# RobotController.net
KiCad netlist of a schematic drawn in EAGLE
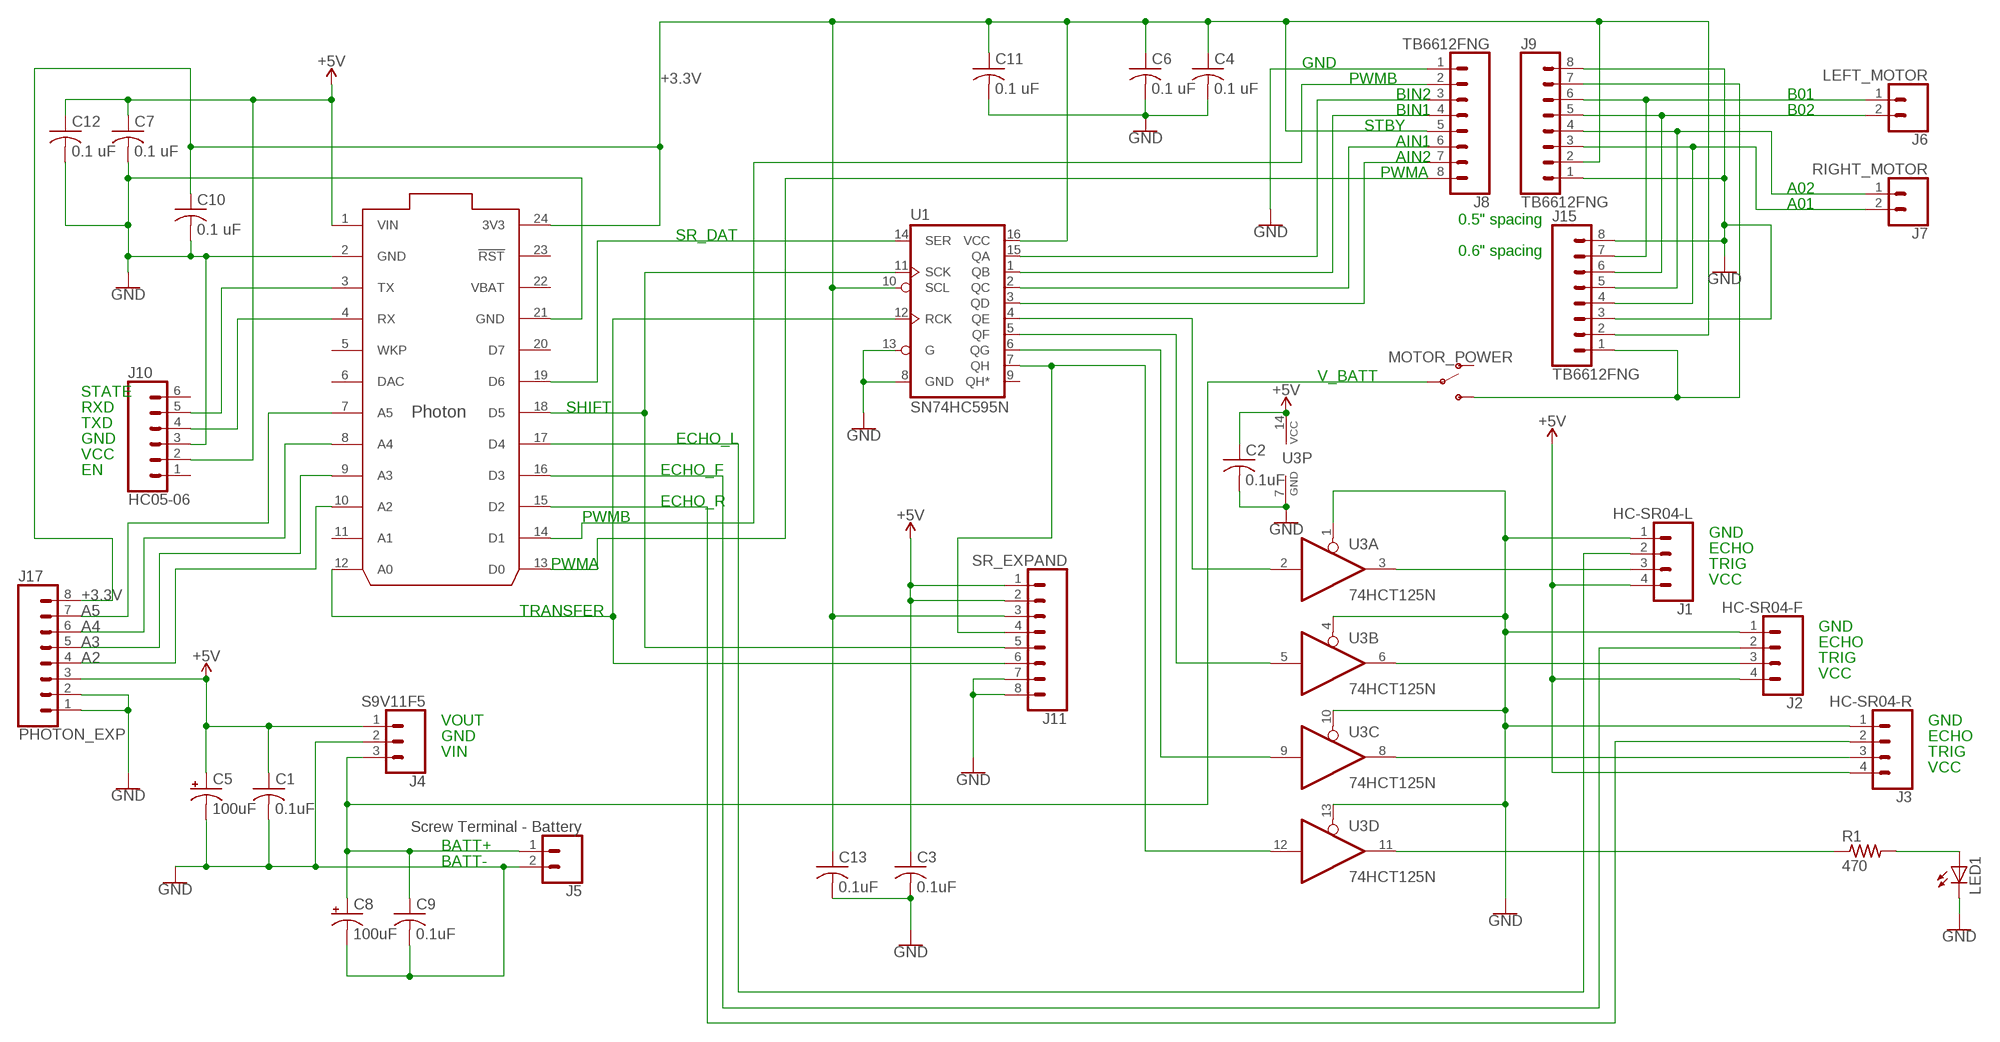
[diagram p0: schematic, sheet 1]

(export (version "E")
  (design (tool "Eeschema 10.0.6"))
  (components
    (comp (ref "C1")
      (value "0.1uF")
      (footprint "eagle-import:C025-024X044")
      (libsource (lib "eagle-import") (part "C-US025-024X044"))
    )
    (comp (ref "C2")
      (value "0.1uF")
      (footprint "eagle-import:C025-024X044")
      (libsource (lib "eagle-import") (part "C-US025-024X044"))
    )
    (comp (ref "C3")
      (value "0.1uF")
      (footprint "eagle-import:C025-024X044")
      (libsource (lib "eagle-import") (part "C-US025-024X044"))
    )
    (comp (ref "C4")
      (value "0.1 uF")
      (footprint "eagle-import:C025-024X044")
      (libsource (lib "eagle-import") (part "C-US025-024X044"))
    )
    (comp (ref "C5")
      (value "100uF")
      (footprint "eagle-import:E2,5-6E")
      (libsource (lib "eagle-import") (part "CPOL-USE2,5-6E"))
    )
    (comp (ref "C6")
      (value "0.1 uF")
      (footprint "eagle-import:C025-024X044")
      (libsource (lib "eagle-import") (part "C-US025-024X044"))
    )
    (comp (ref "C7")
      (value "0.1 uF")
      (footprint "eagle-import:C025-024X044")
      (libsource (lib "eagle-import") (part "C-US025-024X044"))
    )
    (comp (ref "C8")
      (value "100uF")
      (footprint "eagle-import:E2,5-6E")
      (libsource (lib "eagle-import") (part "CPOL-USE2,5-6E"))
    )
    (comp (ref "C9")
      (value "0.1uF")
      (footprint "eagle-import:C025-024X044")
      (libsource (lib "eagle-import") (part "C-US025-024X044"))
    )
    (comp (ref "C10")
      (value "0.1 uF")
      (footprint "eagle-import:C025-024X044")
      (libsource (lib "eagle-import") (part "C-US025-024X044"))
    )
    (comp (ref "C11")
      (value "0.1 uF")
      (footprint "eagle-import:C025-024X044")
      (libsource (lib "eagle-import") (part "C-US025-024X044"))
    )
    (comp (ref "C12")
      (value "0.1 uF")
      (footprint "eagle-import:C025-024X044")
      (libsource (lib "eagle-import") (part "C-US025-024X044"))
    )
    (comp (ref "C13")
      (value "0.1uF")
      (footprint "eagle-import:C025-024X044")
      (libsource (lib "eagle-import") (part "C-US025-024X044"))
    )
    (comp (ref "J1")
      (value "HC-SR04-L")
      (footprint "eagle-import:1X04")
      (libsource (lib "eagle-import") (part "CONN_04"))
    )
    (comp (ref "J2")
      (value "HC-SR04-F")
      (footprint "eagle-import:1X04")
      (libsource (lib "eagle-import") (part "CONN_04"))
    )
    (comp (ref "J3")
      (value "HC-SR04-R")
      (footprint "eagle-import:1X04")
      (libsource (lib "eagle-import") (part "CONN_04"))
    )
    (comp (ref "J4")
      (value "S9V11F5")
      (footprint "eagle-import:1X03")
      (libsource (lib "eagle-import") (part "CONN_03"))
    )
    (comp (ref "J5")
      (value "Screw Terminal - Battery")
      (footprint "eagle-import:SCREWTERMINAL-3.5MM-2")
      (libsource (lib "eagle-import") (part "CONN_023.5MM"))
    )
    (comp (ref "J6")
      (value "LEFT_MOTOR")
      (footprint "eagle-import:SCREWTERMINAL-3.5MM-2")
      (libsource (lib "eagle-import") (part "CONN_023.5MM"))
    )
    (comp (ref "J7")
      (value "RIGHT_MOTOR")
      (footprint "eagle-import:SCREWTERMINAL-3.5MM-2")
      (libsource (lib "eagle-import") (part "CONN_023.5MM"))
    )
    (comp (ref "J8")
      (value "TB6612FNG")
      (footprint "eagle-import:1X08")
      (libsource (lib "eagle-import") (part "CONN_08{dblquote}"))
    )
    (comp (ref "J9")
      (value "TB6612FNG")
      (footprint "eagle-import:1X08")
      (libsource (lib "eagle-import") (part "CONN_08{dblquote}"))
    )
    (comp (ref "J10")
      (value "HC05-06")
      (footprint "eagle-import:1X06")
      (libsource (lib "eagle-import") (part "CONN_06SILK_FEMALE_PTH"))
    )
    (comp (ref "J11")
      (value "SR_EXPAND")
      (footprint "eagle-import:1X08")
      (libsource (lib "eagle-import") (part "CONN_08{dblquote}"))
    )
    (comp (ref "J15")
      (value "TB6612FNG")
      (footprint "eagle-import:1X08")
      (libsource (lib "eagle-import") (part "CONN_08{dblquote}"))
    )
    (comp (ref "J17")
      (value "PHOTON_EXP")
      (footprint "eagle-import:1X08")
      (libsource (lib "eagle-import") (part "CONN_08{dblquote}"))
    )
    (comp (ref "LED1")
      (value "LED5MM")
      (footprint "eagle-import:LED5MM")
      (libsource (lib "eagle-import") (part "LED5MM"))
    )
    (comp (ref "MOTOR_POWER")
      (value "SWITCH-SPDT-PTH-11.6X4.0MM")
      (footprint "eagle-import:SWITCH_SPDT_PTH_11.6X4.0MM")
      (libsource (lib "eagle-import") (part "SWITCH-SPDT-PTH-11.6X4.0MM"))
    )
    (comp (ref "R1")
      (value "470")
      (footprint "eagle-import:0207_10")
      (libsource (lib "eagle-import") (part "R-US_0207/10"))
    )
    (comp (ref "U$1")
      (value "PHOTON_WITH_HEADERS")
      (footprint "eagle-import:PHOTON")
      (libsource (lib "eagle-import") (part "PHOTON_WITH_HEADERS"))
    )
    (comp (ref "U1")
      (value "SN74HC595N")
      (footprint "eagle-import:DIP16")
      (libsource (lib "eagle-import") (part "74595NHC"))
    )
    (comp (ref "U3")
      (value "74HCT125N")
      (footprint "eagle-import:DIL14")
      (libsource (lib "eagle-import") (part "74125NHCT"))
    )
  )
  (nets
    (net (code "1") (name "+5V") (class "Default")
      (node (ref "C1") (pin "1") (pinfunction "1_1") (pintype "passive"))
      (node (ref "C12") (pin "1") (pinfunction "1_1") (pintype "passive"))
      (node (ref "C2") (pin "1") (pinfunction "1_1") (pintype "passive"))
      (node (ref "C3") (pin "1") (pinfunction "1_1") (pintype "passive"))
      (node (ref "C5") (pin "+") (pinfunction "+_+") (pintype "passive"))
      (node (ref "C7") (pin "1") (pinfunction "1_1") (pintype "passive"))
      (node (ref "J1") (pin "4") (pinfunction "4_4") (pintype "passive"))
      (node (ref "J10") (pin "2") (pinfunction "2_2") (pintype "passive"))
      (node (ref "J11") (pin "1") (pinfunction "1_1") (pintype "passive"))
      (node (ref "J11") (pin "2") (pinfunction "2_2") (pintype "passive"))
      (node (ref "J17") (pin "3") (pinfunction "3_3") (pintype "passive"))
      (node (ref "J2") (pin "4") (pinfunction "4_4") (pintype "passive"))
      (node (ref "J3") (pin "4") (pinfunction "4_4") (pintype "passive"))
      (node (ref "J4") (pin "1") (pinfunction "1_1") (pintype "passive"))
      (node (ref "U$1") (pin "1") (pinfunction "VIN_1") (pintype "power_in"))
      (node (ref "U3") (pin "14") (pinfunction "VCC_14") (pintype "power_in"))
    )
    (net (code "2") (name "/+3.3V") (class "Default")
      (node (ref "C10") (pin "1") (pinfunction "1_1") (pintype "passive"))
      (node (ref "C11") (pin "1") (pinfunction "1_1") (pintype "passive"))
      (node (ref "C13") (pin "1") (pinfunction "1_1") (pintype "passive"))
      (node (ref "C4") (pin "1") (pinfunction "1_1") (pintype "passive"))
      (node (ref "C6") (pin "1") (pinfunction "1_1") (pintype "passive"))
      (node (ref "J11") (pin "3") (pinfunction "3_3") (pintype "passive"))
      (node (ref "J15") (pin "2") (pinfunction "2_2") (pintype "passive"))
      (node (ref "J17") (pin "8") (pinfunction "8_8") (pintype "passive"))
      (node (ref "J8") (pin "5") (pinfunction "5_5") (pintype "passive"))
      (node (ref "J9") (pin "2") (pinfunction "2_2") (pintype "passive"))
      (node (ref "U$1") (pin "24") (pinfunction "3V3_24") (pintype "power_in"))
      (node (ref "U1") (pin "10") (pinfunction "SCL_10") (pintype "input"))
      (node (ref "U1") (pin "16") (pinfunction "VCC_16") (pintype "power_in"))
    )
    (net (code "3") (name "/A2") (class "Default")
      (node (ref "J17") (pin "4") (pinfunction "4_4") (pintype "passive"))
      (node (ref "U$1") (pin "10") (pinfunction "A2_10") (pintype "bidirectional"))
    )
    (net (code "4") (name "/A3") (class "Default")
      (node (ref "J17") (pin "5") (pinfunction "5_5") (pintype "passive"))
      (node (ref "U$1") (pin "9") (pinfunction "A3_9") (pintype "bidirectional"))
    )
    (net (code "5") (name "/A4") (class "Default")
      (node (ref "J17") (pin "6") (pinfunction "6_6") (pintype "passive"))
      (node (ref "U$1") (pin "8") (pinfunction "A4_8") (pintype "bidirectional"))
    )
    (net (code "6") (name "/A5") (class "Default")
      (node (ref "J17") (pin "7") (pinfunction "7_7") (pintype "passive"))
      (node (ref "U$1") (pin "7") (pinfunction "A5_7") (pintype "bidirectional"))
    )
    (net (code "7") (name "/VBAT") (class "Default")
      (node (ref "U$1") (pin "22") (pinfunction "VBAT_22") (pintype "power_in"))
    )
    (net (code "8") (name "GND") (class "Default")
      (node (ref "C1") (pin "2") (pinfunction "2_2") (pintype "passive"))
      (node (ref "C10") (pin "2") (pinfunction "2_2") (pintype "passive"))
      (node (ref "C11") (pin "2") (pinfunction "2_2") (pintype "passive"))
      (node (ref "C12") (pin "2") (pinfunction "2_2") (pintype "passive"))
      (node (ref "C13") (pin "2") (pinfunction "2_2") (pintype "passive"))
      (node (ref "C2") (pin "2") (pinfunction "2_2") (pintype "passive"))
      (node (ref "C3") (pin "2") (pinfunction "2_2") (pintype "passive"))
      (node (ref "C4") (pin "2") (pinfunction "2_2") (pintype "passive"))
      (node (ref "C5") (pin "-") (pinfunction "-_-") (pintype "passive"))
      (node (ref "C6") (pin "2") (pinfunction "2_2") (pintype "passive"))
      (node (ref "C7") (pin "2") (pinfunction "2_2") (pintype "passive"))
      (node (ref "C8") (pin "-") (pinfunction "-_-") (pintype "passive"))
      (node (ref "C9") (pin "2") (pinfunction "2_2") (pintype "passive"))
      (node (ref "J1") (pin "1") (pinfunction "1_1") (pintype "passive"))
      (node (ref "J10") (pin "3") (pinfunction "3_3") (pintype "passive"))
      (node (ref "J11") (pin "7") (pinfunction "7_7") (pintype "passive"))
      (node (ref "J11") (pin "8") (pinfunction "8_8") (pintype "passive"))
      (node (ref "J15") (pin "3") (pinfunction "3_3") (pintype "passive"))
      (node (ref "J15") (pin "8") (pinfunction "8_8") (pintype "passive"))
      (node (ref "J17") (pin "1") (pinfunction "1_1") (pintype "passive"))
      (node (ref "J17") (pin "2") (pinfunction "2_2") (pintype "passive"))
      (node (ref "J2") (pin "1") (pinfunction "1_1") (pintype "passive"))
      (node (ref "J3") (pin "1") (pinfunction "1_1") (pintype "passive"))
      (node (ref "J4") (pin "2") (pinfunction "2_2") (pintype "passive"))
      (node (ref "J5") (pin "2") (pinfunction "2_2") (pintype "passive"))
      (node (ref "J8") (pin "1") (pinfunction "1_1") (pintype "passive"))
      (node (ref "J9") (pin "1") (pinfunction "1_1") (pintype "passive"))
      (node (ref "J9") (pin "8") (pinfunction "8_8") (pintype "passive"))
      (node (ref "LED1") (pin "K") (pinfunction "C_K") (pintype "passive"))
      (node (ref "U$1") (pin "2") (pinfunction "GND_2") (pintype "power_in"))
      (node (ref "U$1") (pin "21") (pinfunction "GND_21") (pintype "power_in"))
      (node (ref "U1") (pin "13") (pinfunction "G_13") (pintype "input"))
      (node (ref "U1") (pin "8") (pinfunction "GND_8") (pintype "power_in"))
      (node (ref "U3") (pin "1") (pinfunction "OE_1") (pintype "input"))
      (node (ref "U3") (pin "10") (pinfunction "OE_10") (pintype "input"))
      (node (ref "U3") (pin "13") (pinfunction "OE_13") (pintype "input"))
      (node (ref "U3") (pin "4") (pinfunction "OE_4") (pintype "input"))
      (node (ref "U3") (pin "7") (pinfunction "GND_7") (pintype "power_in"))
    )
    (net (code "9") (name "Net-(J15-Pad4)") (class "Default")
      (node (ref "J15") (pin "4") (pinfunction "4_4") (pintype "passive"))
      (node (ref "J7") (pin "2") (pinfunction "2_2") (pintype "passive"))
      (node (ref "J9") (pin "3") (pinfunction "3_3") (pintype "passive"))
    )
    (net (code "10") (name "Net-(J15-Pad5)") (class "Default")
      (node (ref "J15") (pin "5") (pinfunction "5_5") (pintype "passive"))
      (node (ref "J7") (pin "1") (pinfunction "1_1") (pintype "passive"))
      (node (ref "J9") (pin "4") (pinfunction "4_4") (pintype "passive"))
    )
    (net (code "11") (name "Net-(J15-Pad6)") (class "Default")
      (node (ref "J15") (pin "6") (pinfunction "6_6") (pintype "passive"))
      (node (ref "J6") (pin "2") (pinfunction "2_2") (pintype "passive"))
      (node (ref "J9") (pin "5") (pinfunction "5_5") (pintype "passive"))
    )
    (net (code "12") (name "Net-(J15-Pad7)") (class "Default")
      (node (ref "J15") (pin "7") (pinfunction "7_7") (pintype "passive"))
      (node (ref "J6") (pin "1") (pinfunction "1_1") (pintype "passive"))
      (node (ref "J9") (pin "6") (pinfunction "6_6") (pintype "passive"))
    )
    (net (code "13") (name "Net-(LED1-PadA)") (class "Default")
      (node (ref "LED1") (pin "A") (pinfunction "A_A") (pintype "passive"))
      (node (ref "R1") (pin "2") (pinfunction "2_2") (pintype "passive"))
    )
    (net (code "14") (name "Net-(MOTOR_POWER-P)") (class "Default")
      (node (ref "C8") (pin "+") (pinfunction "+_+") (pintype "passive"))
      (node (ref "C9") (pin "1") (pinfunction "1_1") (pintype "passive"))
      (node (ref "J4") (pin "3") (pinfunction "3_3") (pintype "passive"))
      (node (ref "J5") (pin "1") (pinfunction "1_1") (pintype "passive"))
      (node (ref "MOTOR_POWER") (pin "2") (pinfunction "P_2") (pintype "passive"))
    )
    (net (code "15") (name "Net-(MOTOR_POWER-S)") (class "Default")
      (node (ref "J15") (pin "1") (pinfunction "1_1") (pintype "passive"))
      (node (ref "J9") (pin "7") (pinfunction "7_7") (pintype "passive"))
      (node (ref "MOTOR_POWER") (pin "3") (pinfunction "S_3") (pintype "passive"))
    )
    (net (code "16") (name "Net-(U$1-A0)") (class "Default")
      (node (ref "J11") (pin "6") (pinfunction "6_6") (pintype "passive"))
      (node (ref "U$1") (pin "12") (pinfunction "A0_12") (pintype "bidirectional"))
      (node (ref "U1") (pin "12") (pinfunction "RCK_12") (pintype "input"))
    )
    (net (code "17") (name "Net-(U$1-D0)") (class "Default")
      (node (ref "J8") (pin "8") (pinfunction "8_8") (pintype "passive"))
      (node (ref "U$1") (pin "13") (pinfunction "D0_13") (pintype "bidirectional"))
    )
    (net (code "18") (name "Net-(U$1-D1)") (class "Default")
      (node (ref "J8") (pin "2") (pinfunction "2_2") (pintype "passive"))
      (node (ref "U$1") (pin "14") (pinfunction "D1_14") (pintype "bidirectional"))
    )
    (net (code "19") (name "Net-(U$1-D2)") (class "Default")
      (node (ref "J3") (pin "2") (pinfunction "2_2") (pintype "passive"))
      (node (ref "U$1") (pin "15") (pinfunction "D2_15") (pintype "bidirectional"))
    )
    (net (code "20") (name "Net-(U$1-D3)") (class "Default")
      (node (ref "J2") (pin "2") (pinfunction "2_2") (pintype "passive"))
      (node (ref "U$1") (pin "16") (pinfunction "D3_16") (pintype "bidirectional"))
    )
    (net (code "21") (name "Net-(U$1-D4)") (class "Default")
      (node (ref "J1") (pin "2") (pinfunction "2_2") (pintype "passive"))
      (node (ref "U$1") (pin "17") (pinfunction "D4_17") (pintype "bidirectional"))
    )
    (net (code "22") (name "Net-(U$1-D5)") (class "Default")
      (node (ref "J11") (pin "5") (pinfunction "5_5") (pintype "passive"))
      (node (ref "U$1") (pin "18") (pinfunction "D5_18") (pintype "bidirectional"))
      (node (ref "U1") (pin "11") (pinfunction "SCK_11") (pintype "input"))
    )
    (net (code "23") (name "Net-(U$1-D6)") (class "Default")
      (node (ref "U$1") (pin "19") (pinfunction "D6_19") (pintype "bidirectional"))
      (node (ref "U1") (pin "14") (pinfunction "SER_14") (pintype "input"))
    )
    (net (code "24") (name "Net-(U$1-RX)") (class "Default")
      (node (ref "J10") (pin "4") (pinfunction "4_4") (pintype "passive"))
      (node (ref "U$1") (pin "4") (pinfunction "RX_4") (pintype "bidirectional"))
    )
    (net (code "25") (name "Net-(U$1-TX)") (class "Default")
      (node (ref "J10") (pin "5") (pinfunction "5_5") (pintype "passive"))
      (node (ref "U$1") (pin "3") (pinfunction "TX_3") (pintype "bidirectional"))
    )
    (net (code "26") (name "Net-(U1-QA)") (class "Default")
      (node (ref "J8") (pin "3") (pinfunction "3_3") (pintype "passive"))
      (node (ref "U1") (pin "15") (pinfunction "QA_15") (pintype "tri_state"))
    )
    (net (code "27") (name "Net-(U1-QB)") (class "Default")
      (node (ref "J8") (pin "4") (pinfunction "4_4") (pintype "passive"))
      (node (ref "U1") (pin "1") (pinfunction "QB_1") (pintype "tri_state"))
    )
    (net (code "28") (name "Net-(U1-QC)") (class "Default")
      (node (ref "J8") (pin "6") (pinfunction "6_6") (pintype "passive"))
      (node (ref "U1") (pin "2") (pinfunction "QC_2") (pintype "tri_state"))
    )
    (net (code "29") (name "Net-(U1-QD)") (class "Default")
      (node (ref "J8") (pin "7") (pinfunction "7_7") (pintype "passive"))
      (node (ref "U1") (pin "3") (pinfunction "QD_3") (pintype "tri_state"))
    )
    (net (code "30") (name "Net-(U1-QE)") (class "Default")
      (node (ref "U1") (pin "4") (pinfunction "QE_4") (pintype "tri_state"))
      (node (ref "U3") (pin "2") (pinfunction "I_2") (pintype "input"))
    )
    (net (code "31") (name "Net-(U1-QF)") (class "Default")
      (node (ref "U1") (pin "5") (pinfunction "QF_5") (pintype "tri_state"))
      (node (ref "U3") (pin "5") (pinfunction "I_5") (pintype "input"))
    )
    (net (code "32") (name "Net-(U1-QG)") (class "Default")
      (node (ref "U1") (pin "6") (pinfunction "QG_6") (pintype "tri_state"))
      (node (ref "U3") (pin "9") (pinfunction "I_9") (pintype "input"))
    )
    (net (code "33") (name "Net-(U1-QH)") (class "Default")
      (node (ref "J11") (pin "4") (pinfunction "4_4") (pintype "passive"))
      (node (ref "U1") (pin "7") (pinfunction "QH_7") (pintype "tri_state"))
      (node (ref "U3") (pin "12") (pinfunction "I_12") (pintype "input"))
    )
    (net (code "34") (name "Net-(U3A-O)") (class "Default")
      (node (ref "J1") (pin "3") (pinfunction "3_3") (pintype "passive"))
      (node (ref "U3") (pin "3") (pinfunction "O_3") (pintype "tri_state"))
    )
    (net (code "35") (name "Net-(U3B-O)") (class "Default")
      (node (ref "J2") (pin "3") (pinfunction "3_3") (pintype "passive"))
      (node (ref "U3") (pin "6") (pinfunction "O_6") (pintype "tri_state"))
    )
    (net (code "36") (name "Net-(U3C-O)") (class "Default")
      (node (ref "J3") (pin "3") (pinfunction "3_3") (pintype "passive"))
      (node (ref "U3") (pin "8") (pinfunction "O_8") (pintype "tri_state"))
    )
    (net (code "37") (name "Net-(U3D-O)") (class "Default")
      (node (ref "R1") (pin "1") (pinfunction "1_1") (pintype "passive"))
      (node (ref "U3") (pin "11") (pinfunction "O_11") (pintype "tri_state"))
    )
    (net (code "38") (name "unconnected-(J10-Pad1)") (class "Default")
      (node (ref "J10") (pin "1") (pinfunction "1_1") (pintype "passive"))
    )
    (net (code "39") (name "unconnected-(J10-Pad6)") (class "Default")
      (node (ref "J10") (pin "6") (pinfunction "6_6") (pintype "passive"))
    )
    (net (code "40") (name "unconnected-(MOTOR_POWER-O-Pad1)") (class "Default")
      (node (ref "MOTOR_POWER") (pin "1") (pinfunction "O_1") (pintype "passive"))
    )
    (net (code "41") (name "unconnected-(U$1-A1-Pad11)") (class "Default")
      (node (ref "U$1") (pin "11") (pinfunction "A1_11") (pintype "bidirectional"))
    )
    (net (code "42") (name "unconnected-(U$1-D7-Pad20)") (class "Default")
      (node (ref "U$1") (pin "20") (pinfunction "D7_20") (pintype "bidirectional"))
    )
    (net (code "43") (name "unconnected-(U$1-DAC-Pad6)") (class "Default")
      (node (ref "U$1") (pin "6") (pinfunction "DAC_6") (pintype "bidirectional"))
    )
    (net (code "44") (name "unconnected-(U$1-WKP-Pad5)") (class "Default")
      (node (ref "U$1") (pin "5") (pinfunction "WKP_5") (pintype "bidirectional"))
    )
    (net (code "45") (name "unconnected-(U$1-~{RST}-Pad23)") (class "Default")
      (node (ref "U$1") (pin "23") (pinfunction "~{RST}_23") (pintype "bidirectional"))
    )
    (net (code "46") (name "unconnected-(U1-QH*-Pad9)") (class "Default")
      (node (ref "U1") (pin "9") (pinfunction "QH*_9") (pintype "tri_state"))
    )
  )
)
